# Power.net
KiCad netlist of a schematic drawn in Altium Designer
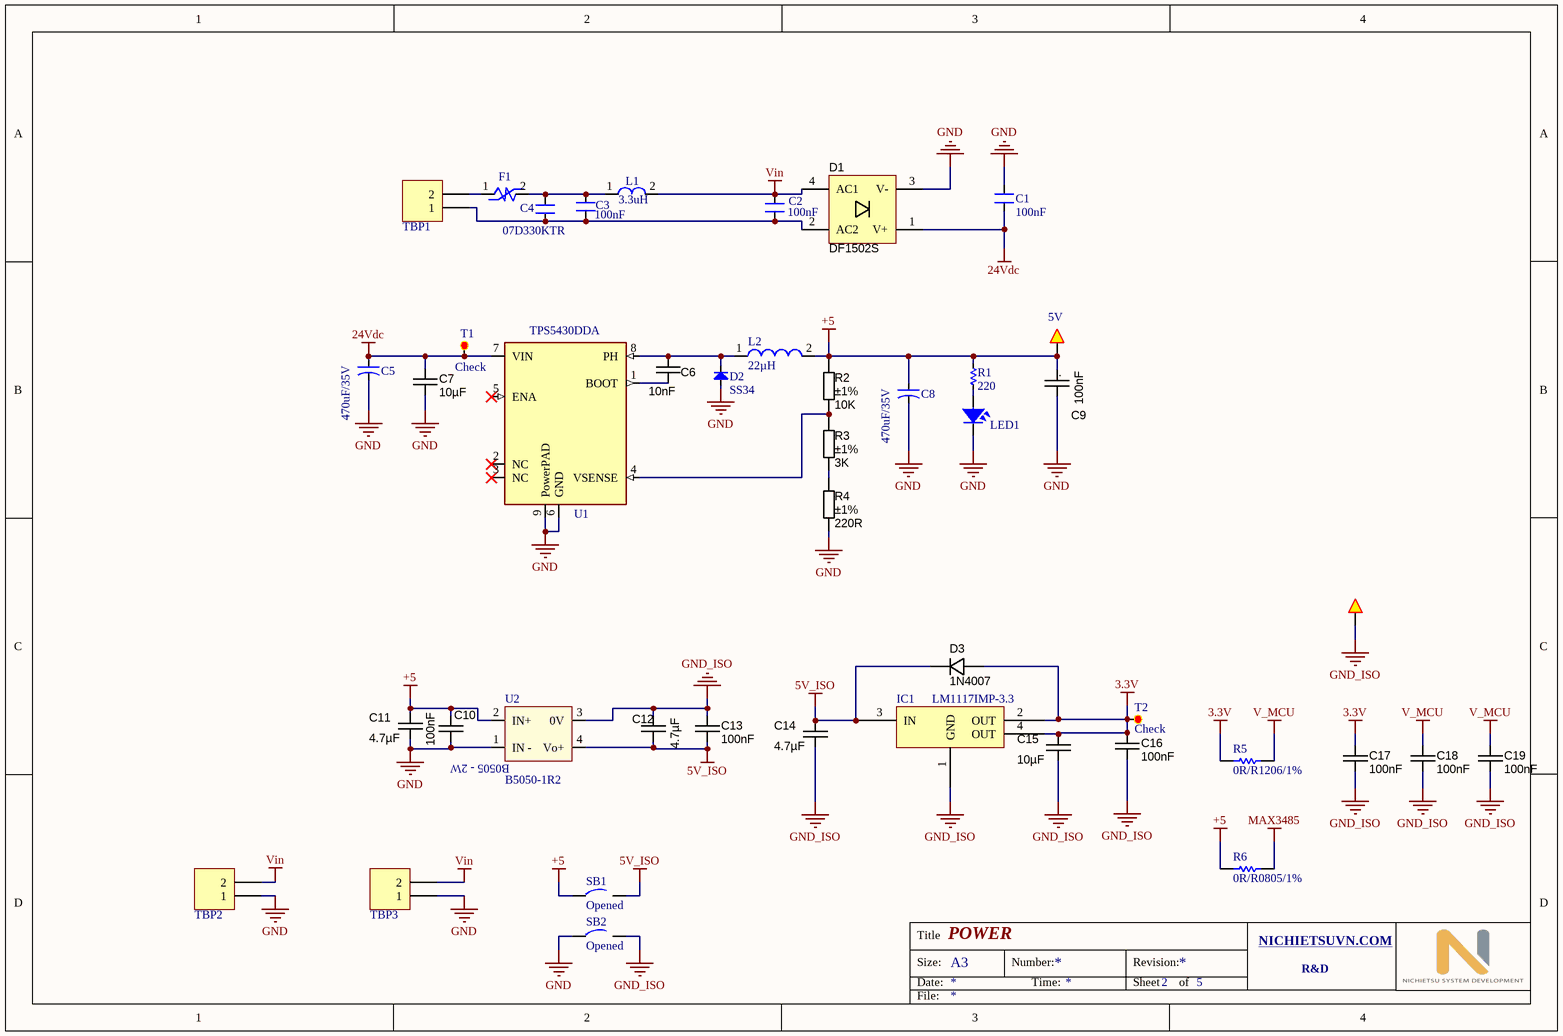
[diagram p0: Power.SchDoc]

(export (version "E")
  (design (tool "Eeschema 10.0.6"))
  (components
    (comp (ref "B1")
      (value "TX1")
      (footprint "Test")
      (description "WR-PHD 2.54 mm Angled Socket Header")
      (fields
        (field (name "MANUFACTURER") "Würth Elektronik eiSos GmbH")
        (field (name "PARTNO") "613002143121")
        (field (name "CREATED BY") "Karrer Zheng")
      )
      (libsource (lib "Nichietsuvn") (part "Test"))
    )
    (comp (ref "C1") (value "100nF") (footprint "CN-SMD-1206") (libsource (lib "thu vien 3d") (part "CN")))
    (comp (ref "C2") (value "100nF") (footprint "CN-SMD-1206") (libsource (lib "thu vien 3d") (part "CN")))
    (comp (ref "C3") (value "100nF") (footprint "CN2.5") (libsource (lib "thu vien 3d") (part "CN")))
    (comp (ref "C4") (value "07D330KTR") (footprint "CN2-T") (libsource (lib "thu vien 3d") (part "CN")))
    (comp (ref "C5")
      (value "470uF/35V")
      (footprint "CA-ALU-6.3")
      (description "Capacitor (Semiconductor SIM Model)")
      (fields (field (name "PUBLISHER") "Altium Limited"))
      (libsource (lib "thu vien 3d") (part "CN-ALU-DIP"))
    )
    (comp (ref "C6")
      (value "10nF")
      (footprint "CAPC1608X90N")
      (description "10000pF ±10% 50V Ceramic Capacitor X7R 0603 (1608 Metric)")
      (fields (field (name "TOLERANCE") "±10%"))
      (libsource (lib "SangMV") (part "CAPC_10000pF_0603_50V_10%"))
    )
    (comp (ref "C7")
      (value "10µF")
      (footprint "CAPC2012X135N")
      (description "10µF ±10% 25V Ceramic Capacitor X7R 1206 (3216 Metric)")
      (fields (field (name "TOLERANCE") "±10%") (field (name "MANUFACTURER PART NUMBER") "TMK316AB7106KLHT"))
      (libsource (lib "All Library") (part "CAPC_10uF_0805_X7R_25V_10%"))
    )
    (comp (ref "C8")
      (value "470uF/35V")
      (footprint "CA-ALU-6.3")
      (description "Capacitor (Semiconductor SIM Model)")
      (fields (field (name "PUBLISHER") "Altium Limited"))
      (libsource (lib "thu vien 3d") (part "CN-ALU-DIP"))
    )
    (comp (ref "C9")
      (value "100nF")
      (footprint "CAPC2012X135N")
      (description "0.1µF ±10% 50V Ceramic Capacitor X7R 0805 (2012 Metric)")
      (fields (field (name "TOLERANCE") "±10%") (field (name "MANUFACTURER PART NUMBER") "CL21B104KBFXPJE"))
      (libsource (lib "SangMV") (part "CAPC_100nF_0805_X7R_50V_10%"))
    )
    (comp (ref "C10")
      (value "100nF")
      (footprint "CAPC1608X90N")
      (description "0.1µF ±10% 50V Ceramic Capacitor X7R 0603 (1608 Metric)")
      (fields (field (name "TOLERANCE") "±10%"))
      (libsource (lib "All Library") (part "CAPC_100nF_0603_X7R_50V_10%"))
    )
    (comp (ref "C11")
      (value "4.7µF")
      (footprint "CAPC2012X135N")
      (description "4.7µF ±10% 50V Ceramic Capacitor X7R 0805 (2012 Metric)")
      (fields
        (field (name "TOLERANCE") "±10%")
        (field (name "MANUFACTURER PART NUMBER") "CGA4J1X7R1H475K125AE")
      )
      (libsource (lib "All Library") (part "CAPC_4.7uF_0805_X7R_50V_10%"))
    )
    (comp (ref "C12")
      (value "4.7µF")
      (footprint "CAPC2012X135N")
      (description "4.7µF ±10% 50V Ceramic Capacitor X7R 0805 (2012 Metric)")
      (fields
        (field (name "TOLERANCE") "±10%")
        (field (name "MANUFACTURER PART NUMBER") "CGA4J1X7R1H475K125AE")
      )
      (libsource (lib "All Library") (part "CAPC_4.7uF_0805_X7R_50V_10%"))
    )
    (comp (ref "C13")
      (value "100nF")
      (footprint "CAPC1608X90N")
      (description "0.1µF ±10% 50V Ceramic Capacitor X7R 0603 (1608 Metric)")
      (fields (field (name "TOLERANCE") "±10%"))
      (libsource (lib "All Library") (part "CAPC_100nF_0603_X7R_50V_10%"))
    )
    (comp (ref "C14")
      (value "4.7µF")
      (footprint "CAPC2012X135N")
      (description "4.7µF ±10% 50V Ceramic Capacitor X7R 0805 (2012 Metric)")
      (fields
        (field (name "TOLERANCE") "±10%")
        (field (name "MANUFACTURER PART NUMBER") "CGA4J1X7R1H475K125AE")
      )
      (libsource (lib "All Library") (part "CAPC_4.7uF_0805_X7R_50V_10%"))
    )
    (comp (ref "C15")
      (value "10µF")
      (footprint "CAPC2012X135N")
      (description "4.7µF ±10% 50V Ceramic Capacitor X7R 0805 (2012 Metric)")
      (fields
        (field (name "TOLERANCE") "±10%")
        (field (name "MANUFACTURER PART NUMBER") "CGA4J1X7R1H475K125AE")
      )
      (libsource (lib "All Library") (part "CAPC_4.7uF_0805_X7R_50V_10%"))
    )
    (comp (ref "C16")
      (value "100nF")
      (footprint "CAPC1608X90N")
      (description "0.1µF ±10% 50V Ceramic Capacitor X7R 0603 (1608 Metric)")
      (fields (field (name "TOLERANCE") "±10%"))
      (libsource (lib "All Library") (part "CAPC_100nF_0603_X7R_50V_10%"))
    )
    (comp (ref "C17")
      (value "100nF")
      (footprint "CAPC1608X90N")
      (description "0.1µF ±10% 50V Ceramic Capacitor X7R 0603 (1608 Metric)")
      (fields (field (name "TOLERANCE") "±10%"))
      (libsource (lib "All Library") (part "CAPC_100nF_0603_X7R_50V_10%"))
    )
    (comp (ref "C18")
      (value "100nF")
      (footprint "CAPC1608X90N")
      (description "0.1µF ±10% 50V Ceramic Capacitor X7R 0603 (1608 Metric)")
      (fields (field (name "TOLERANCE") "±10%"))
      (libsource (lib "All Library") (part "CAPC_100nF_0603_X7R_50V_10%"))
    )
    (comp (ref "C19")
      (value "100nF")
      (footprint "CAPC1608X90N")
      (description "0.1µF ±10% 50V Ceramic Capacitor X7R 0603 (1608 Metric)")
      (fields (field (name "TOLERANCE") "±10%"))
      (libsource (lib "All Library") (part "CAPC_100nF_0603_X7R_50V_10%"))
    )
    (comp (ref "Check1")
      (value "5V")
      (footprint "SMD-2")
      (description "WR-PHD 2.54 mm Angled Socket Header")
      (fields
        (field (name "MANUFACTURER") "Würth Elektronik eiSos GmbH")
        (field (name "PARTNO") "613002143121")
        (field (name "CREATED BY") "Karrer Zheng")
      )
      (libsource (lib "Nichietsuvn") (part "Test"))
    )
    (comp (ref "D1")
      (value "DF1502S")
      (footprint "DIODE_DF_S")
      (description "Bridge Rectifier Single Phase Standard 200V Surface Mount DF-S")
      (libsource (lib "PCB_ESP32_Extern") (part "DIODE_DF1502S"))
    )
    (comp (ref "D2")
      (value "SS34")
      (footprint "DIO-SMD-106")
      (description "Default Diode")
      (fields (field (name "PUBLISHER") "Altium Limited"))
      (libsource (lib "thu vien 3d") (part "Diode SMD"))
    )
    (comp (ref "D3")
      (value "1N4007")
      (footprint "DO-214AC")
      (description "Diode  Standard Rectifier SMD 1000V 1A SMA")
      (libsource (lib "All Library") (part "DIODE_1N4007"))
    )
    (comp (ref "F1") (value "RUEF185") (footprint "RUEF165") (libsource (lib "All Library") (part "RUEF185")))
    (comp (ref "IC1")
      (value "LM1117IMP-3.3")
      (footprint "SOT223")
      (description "Linear Voltage Regulator IC  1 Output  800mA SOT-223")
      (fields
        (field (name "MANUFACTURER") "Texas Instruments")
        (field (name "MANUFACTURER PART NUMBER") "LM1117IMP-3.3/NOPB")
      )
      (libsource (lib "All Library") (part "IC_LM1117IMP-3.3"))
    )
    (comp (ref "L1")
      (value "3.3uH")
      (footprint "L-SMD-M-7.3x4.5")
      (fields
        (field (name "PARTNO") "78477010")
        (field (name "MANUFACTURER") "Wurth Elektronik")
        (field (name "CREATED BY") "Baojun Chen")
      )
      (libsource (lib "thu vien 3d") (part "L-SMD-1"))
    )
    (comp (ref "L2")
      (value "22µH")
      (footprint "IND_COIL_8D43")
      (description "22µH Shielded Wirewound Inductor 950mA 380mOhm Max Nonstandard")
      (libsource (lib "SangMV") (part "INDC_SMD_22uH_8D43"))
    )
    (comp (ref "LED1")
      (value "LED")
      (footprint "LED-0805-Blue")
      (libsource (lib "thu vien 3d") (part "LED SMD"))
    )
    (comp (ref "R1")
      (value "220")
      (footprint "RES-SMD-0603")
      (description "Resistor")
      (fields
        (field (name "MANUFACTURER") "Generic Components")
        (field (name "PUBLISHER") "Altium Hobart Technology Centre")
      )
      (libsource (lib "thu vien 3d") (part "Res-SMD"))
    )
    (comp (ref "R2")
      (value "10K")
      (footprint "RESC1608X55N")
      (fields
        (field (name "MANUFACTURER") "Stackpole Electronics Inc")
        (field (name "MANUFACTURER PART NUMBER") "RMCF0603FT10K0")
        (field (name "TOLERANCE") "±1%")
        (field (name "Comment") "10K_0603_1%")
      )
      (libsource (lib "SangMV") (part "RES_10K_0603_1%"))
    )
    (comp (ref "R3")
      (value "3K")
      (footprint "RESC1608X55N")
      (description "3 kOhms ±1% 0.1W, 1/10W Chip Resistor 0603 (1608 Metric) Automotive AEC-Q200 Thick Film")
      (fields
        (field (name "MANUFACTURER") "Stackpole Electronics Inc")
        (field (name "MANUFACTURER PART NUMBER") "RMCF0603FT3K00")
        (field (name "TOLERANCE") "±1%")
      )
      (libsource (lib "SangMV") (part "RES_3K_0603_1%"))
    )
    (comp (ref "R4")
      (value "220R")
      (footprint "RESC1608X55N")
      (description "220 Ohms ±1% 0.1W, 1/10W Chip Resistor 0603 (1608 Metric) Automotive AEC-Q200 Thick Film")
      (fields
        (field (name "MANUFACTURER") "Stackpole Electronics Inc")
        (field (name "MANUFACTURER PART NUMBER") "RMCF0603FT220R")
        (field (name "TOLERANCE") "±1%")
      )
      (libsource (lib "SangMV") (part "RES_220R_0603_1%"))
    )
    (comp (ref "R5")
      (value "0R/R1206/1%")
      (footprint "R1206")
      (description "RES SMD 0.0 OHM JUMPER 1/4W 1206")
      (fields
        (field (name "MANUFACTURER") "Bourns Inc.")
        (field (name "MANUFACTURER PART NUMBER") "CR1206-J/-000ELF")
      )
      (libsource (lib "All Library") (part "RES_0R/R1206/1%"))
    )
    (comp (ref "R6")
      (value "0R/R0805/1%")
      (footprint "R0805")
      (description "RES SMD 0.0 OHM JUMPER 1/8W 0805")
      (fields
        (field (name "MANUFACTURER") "Bourns Inc.")
        (field (name "MANUFACTURER PART NUMBER") "CR0805-J/-000ELF")
      )
      (libsource (lib "All Library") (part "RES_0R/R0805/1%_1"))
    )
    (comp (ref "SB1")
      (value "Opened")
      (footprint "SB_0603")
      (description "Circuit Breaker")
      (fields (field (name "PUBLISHER") "Altium Limited"))
      (libsource (lib "All Library") (part "CircuitBreakerOpen"))
    )
    (comp (ref "SB2")
      (value "Opened")
      (footprint "SB_0603")
      (description "Circuit Breaker")
      (fields (field (name "PUBLISHER") "Altium Limited"))
      (libsource (lib "All Library") (part "CircuitBreakerOpen"))
    )
    (comp (ref "T1")
      (value "Check")
      (footprint "SMD_1.5")
      (description "WR-PHD 2.54 mm Angled Socket Header")
      (fields
        (field (name "MANUFACTURER") "Würth Elektronik eiSos GmbH")
        (field (name "PARTNO") "613002143121")
        (field (name "CREATED BY") "Karrer Zheng")
      )
      (libsource (lib "All Library") (part "Test"))
    )
    (comp (ref "T2")
      (value "Check")
      (footprint "SMD_1.5")
      (description "WR-PHD 2.54 mm Angled Socket Header")
      (fields
        (field (name "MANUFACTURER") "Würth Elektronik eiSos GmbH")
        (field (name "PARTNO") "613002143121")
        (field (name "CREATED BY") "Karrer Zheng")
      )
      (libsource (lib "All Library") (part "Test"))
    )
    (comp (ref "TBP1")
      (value "WE-Terminal Blocks Plugable Type 691322310002")
      (footprint "Terminal_Blocks_Pluggable_Socket__Right_Angle__3.81_mm_Pitch__2_Position")
      (description "WR-TBL Terminal block - serie 322 - 3.81 mm")
      (libsource (lib "All Library") (part "Terminal_Blocks_Pluggable_Socket__Right_Angle__3.81_mm_Pitch__2_Position"))
    )
    (comp (ref "TBP2")
      (value "WE-Terminal Blocks Plugable Type 691322310002")
      (footprint "Terminal_Blocks_Pluggable_Socket__Right_Angle__3.81_mm_Pitch__2_Position")
      (description "WR-TBL Terminal block - serie 322 - 3.81 mm")
      (libsource (lib "All Library") (part "Terminal_Blocks_Pluggable_Socket__Right_Angle__3.81_mm_Pitch__2_Position"))
    )
    (comp (ref "TBP3")
      (value "WE-Terminal Blocks Plugable Type 691322310002")
      (footprint "Terminal_Blocks_Pluggable_Socket__Right_Angle__3.81_mm_Pitch__2_Position")
      (description "WR-TBL Terminal block - serie 322 - 3.81 mm")
      (libsource (lib "All Library") (part "Terminal_Blocks_Pluggable_Socket__Right_Angle__3.81_mm_Pitch__2_Position"))
    )
    (comp (ref "U1")
      (value "TPS5430DDA")
      (footprint "TPS5430")
      (libsource (lib "Nichietsuvn") (part "TPS5430DDA"))
    )
    (comp (ref "U2")
      (value "B5050-1R2")
      (footprint "B0505_1W")
      (libsource (lib "All Library") (part "B5050-1W"))
    )
  )
  (nets
    (net (code "1") (name "+5") (class "Default")
      (node (ref "C10") (pin "1") (pintype "passive"))
      (node (ref "C11") (pin "2") (pintype "passive"))
      (node (ref "C8") (pin "1") (pinfunction "1_1") (pintype "passive"))
      (node (ref "C9") (pin "1") (pintype "passive"))
      (node (ref "Check1") (pin "1") (pinfunction "1_1") (pintype "passive"))
      (node (ref "L2") (pin "2") (pinfunction "2_2") (pintype "passive"))
      (node (ref "R1") (pin "1") (pinfunction "1_1") (pintype "passive"))
      (node (ref "R2") (pin "2") (pinfunction "2_2") (pintype "passive"))
      (node (ref "R6") (pin "1") (pinfunction "1_1") (pintype "passive"))
      (node (ref "SB1") (pin "1") (pinfunction "1_1") (pintype "passive"))
      (node (ref "U2") (pin "2") (pinfunction "IN+_2") (pintype "passive"))
    )
    (net (code "2") (name "3.3V") (class "Default")
      (node (ref "C15") (pin "2") (pintype "passive"))
      (node (ref "C16") (pin "1") (pintype "passive"))
      (node (ref "C17") (pin "1") (pintype "passive"))
      (node (ref "D3") (pin "A") (pinfunction "A_A") (pintype "passive"))
      (node (ref "IC1") (pin "2") (pinfunction "OUT_2") (pintype "passive"))
      (node (ref "IC1") (pin "4") (pinfunction "OUT_4") (pintype "passive"))
      (node (ref "R5") (pin "1") (pinfunction "1_1") (pintype "passive"))
      (node (ref "T2") (pin "1") (pinfunction "1_1") (pintype "passive"))
    )
    (net (code "3") (name "5V_ISO") (class "Default")
      (node (ref "C12") (pin "1") (pintype "passive"))
      (node (ref "C13") (pin "2") (pintype "passive"))
      (node (ref "C14") (pin "2") (pintype "passive"))
      (node (ref "D3") (pin "C") (pinfunction "C_C") (pintype "passive"))
      (node (ref "IC1") (pin "3") (pinfunction "IN_3") (pintype "passive"))
      (node (ref "SB1") (pin "2") (pinfunction "2_2") (pintype "passive"))
      (node (ref "U2") (pin "4") (pinfunction "Vo+_4") (pintype "passive"))
    )
    (net (code "4") (name "24Vdc") (class "Default")
      (node (ref "C1") (pin "2") (pinfunction "2_2") (pintype "passive"))
      (node (ref "C5") (pin "1") (pinfunction "1_1") (pintype "passive"))
      (node (ref "C7") (pin "2") (pintype "passive"))
      (node (ref "D1") (pin "1") (pinfunction "V+_1") (pintype "passive"))
      (node (ref "T1") (pin "1") (pinfunction "1_1") (pintype "passive"))
      (node (ref "U1") (pin "7") (pinfunction "VIN_7") (pintype "power_in"))
    )
    (net (code "5") (name "GND") (class "Default")
      (node (ref "C1") (pin "1") (pinfunction "1_1") (pintype "passive"))
      (node (ref "C10") (pin "2") (pintype "passive"))
      (node (ref "C11") (pin "1") (pintype "passive"))
      (node (ref "C5") (pin "2") (pinfunction "2_2") (pintype "passive"))
      (node (ref "C7") (pin "1") (pintype "passive"))
      (node (ref "C8") (pin "2") (pinfunction "2_2") (pintype "passive"))
      (node (ref "C9") (pin "2") (pintype "passive"))
      (node (ref "D1") (pin "3") (pinfunction "V-_3") (pintype "passive"))
      (node (ref "D2") (pin "1") (pinfunction "A_1") (pintype "passive"))
      (node (ref "LED1") (pin "2") (pinfunction "2_2") (pintype "passive"))
      (node (ref "R4") (pin "1") (pinfunction "1_1") (pintype "passive"))
      (node (ref "SB2") (pin "1") (pinfunction "1_1") (pintype "passive"))
      (node (ref "TBP2") (pin "1") (pinfunction "1_1") (pintype "passive"))
      (node (ref "TBP3") (pin "1") (pinfunction "1_1") (pintype "passive"))
      (node (ref "U1") (pin "6") (pinfunction "GND_6") (pintype "power_in"))
      (node (ref "U1") (pin "9") (pinfunction "PowerPAD_9") (pintype "power_in"))
      (node (ref "U2") (pin "1") (pinfunction "IN_-_1") (pintype "passive"))
    )
    (net (code "6") (name "GND_ISO") (class "Default")
      (node (ref "B1") (pin "1") (pinfunction "1_1") (pintype "passive"))
      (node (ref "C12") (pin "2") (pintype "passive"))
      (node (ref "C13") (pin "1") (pintype "passive"))
      (node (ref "C14") (pin "1") (pintype "passive"))
      (node (ref "C15") (pin "1") (pintype "passive"))
      (node (ref "C16") (pin "2") (pintype "passive"))
      (node (ref "C17") (pin "2") (pintype "passive"))
      (node (ref "C18") (pin "2") (pintype "passive"))
      (node (ref "C19") (pin "2") (pintype "passive"))
      (node (ref "IC1") (pin "1") (pinfunction "GND_1") (pintype "passive"))
      (node (ref "SB2") (pin "2") (pinfunction "2_2") (pintype "passive"))
      (node (ref "U2") (pin "3") (pinfunction "0V_3") (pintype "passive"))
    )
    (net (code "7") (name "MAX3485") (class "Default")
      (node (ref "R6") (pin "2") (pinfunction "2_2") (pintype "passive"))
    )
    (net (code "8") (name "Net-(C3-Pad2)") (class "Default")
      (node (ref "C3") (pin "2") (pinfunction "2_2") (pintype "passive"))
      (node (ref "C4") (pin "2") (pinfunction "2_2") (pintype "passive"))
      (node (ref "F1") (pin "2") (pinfunction "2_2") (pintype "passive"))
      (node (ref "L1") (pin "1") (pinfunction "1_1") (pintype "passive"))
    )
    (net (code "9") (name "Net-(D1-AC2)") (class "Default")
      (node (ref "C2") (pin "1") (pinfunction "1_1") (pintype "passive"))
      (node (ref "C3") (pin "1") (pinfunction "1_1") (pintype "passive"))
      (node (ref "C4") (pin "1") (pinfunction "1_1") (pintype "passive"))
      (node (ref "D1") (pin "2") (pinfunction "AC2_2") (pintype "passive"))
      (node (ref "TBP1") (pin "1") (pinfunction "1_1") (pintype "passive"))
    )
    (net (code "10") (name "Net-(D2-K)") (class "Default")
      (node (ref "C6") (pin "2") (pintype "passive"))
      (node (ref "D2") (pin "2") (pinfunction "K_2") (pintype "passive"))
      (node (ref "L2") (pin "1") (pinfunction "1_1") (pintype "passive"))
      (node (ref "U1") (pin "8") (pinfunction "PH_8") (pintype "input"))
    )
    (net (code "11") (name "Net-(F1-Pad1)") (class "Default")
      (node (ref "F1") (pin "1") (pinfunction "1_1") (pintype "passive"))
      (node (ref "TBP1") (pin "2") (pinfunction "2_2") (pintype "passive"))
    )
    (net (code "12") (name "Net-(LED1-Pad1)") (class "Default")
      (node (ref "LED1") (pin "1") (pinfunction "1_1") (pintype "passive"))
      (node (ref "R1") (pin "2") (pinfunction "2_2") (pintype "passive"))
    )
    (net (code "13") (name "Net-(R3-Pad1)") (class "Default")
      (node (ref "R3") (pin "1") (pinfunction "1_1") (pintype "passive"))
      (node (ref "R4") (pin "2") (pinfunction "2_2") (pintype "passive"))
    )
    (net (code "14") (name "Net-(U1-BOOT)") (class "Default")
      (node (ref "C6") (pin "1") (pintype "passive"))
      (node (ref "U1") (pin "1") (pinfunction "BOOT_1") (pintype "output"))
    )
    (net (code "15") (name "Net-(U1-VSENSE)") (class "Default")
      (node (ref "R2") (pin "1") (pinfunction "1_1") (pintype "passive"))
      (node (ref "R3") (pin "2") (pinfunction "2_2") (pintype "passive"))
      (node (ref "U1") (pin "4") (pinfunction "VSENSE_4") (pintype "input"))
    )
    (net (code "16") (name "V_MCU") (class "Default")
      (node (ref "C18") (pin "1") (pintype "passive"))
      (node (ref "C19") (pin "1") (pintype "passive"))
      (node (ref "R5") (pin "2") (pinfunction "2_2") (pintype "passive"))
    )
    (net (code "17") (name "Vin") (class "Default")
      (node (ref "C2") (pin "2") (pinfunction "2_2") (pintype "passive"))
      (node (ref "D1") (pin "4") (pinfunction "AC1_4") (pintype "passive"))
      (node (ref "L1") (pin "2") (pinfunction "2_2") (pintype "passive"))
      (node (ref "TBP2") (pin "2") (pinfunction "2_2") (pintype "passive"))
      (node (ref "TBP3") (pin "2") (pinfunction "2_2") (pintype "passive"))
    )
    (net (code "18") (name "unconnected-(U1-ENA-Pad5)") (class "Default")
      (node (ref "U1") (pin "5") (pinfunction "ENA_5") (pintype "input+no_connect"))
    )
    (net (code "19") (name "unconnected-(U1-NC-Pad2)") (class "Default")
      (node (ref "U1") (pin "2") (pinfunction "NC_2") (pintype "passive+no_connect"))
    )
    (net (code "20") (name "unconnected-(U1-NC-Pad3)") (class "Default")
      (node (ref "U1") (pin "3") (pinfunction "NC_3") (pintype "passive+no_connect"))
    )
  )
)
